# CH32V205RCT-R0.net
KiCad netlist of a schematic drawn in Altium Designer
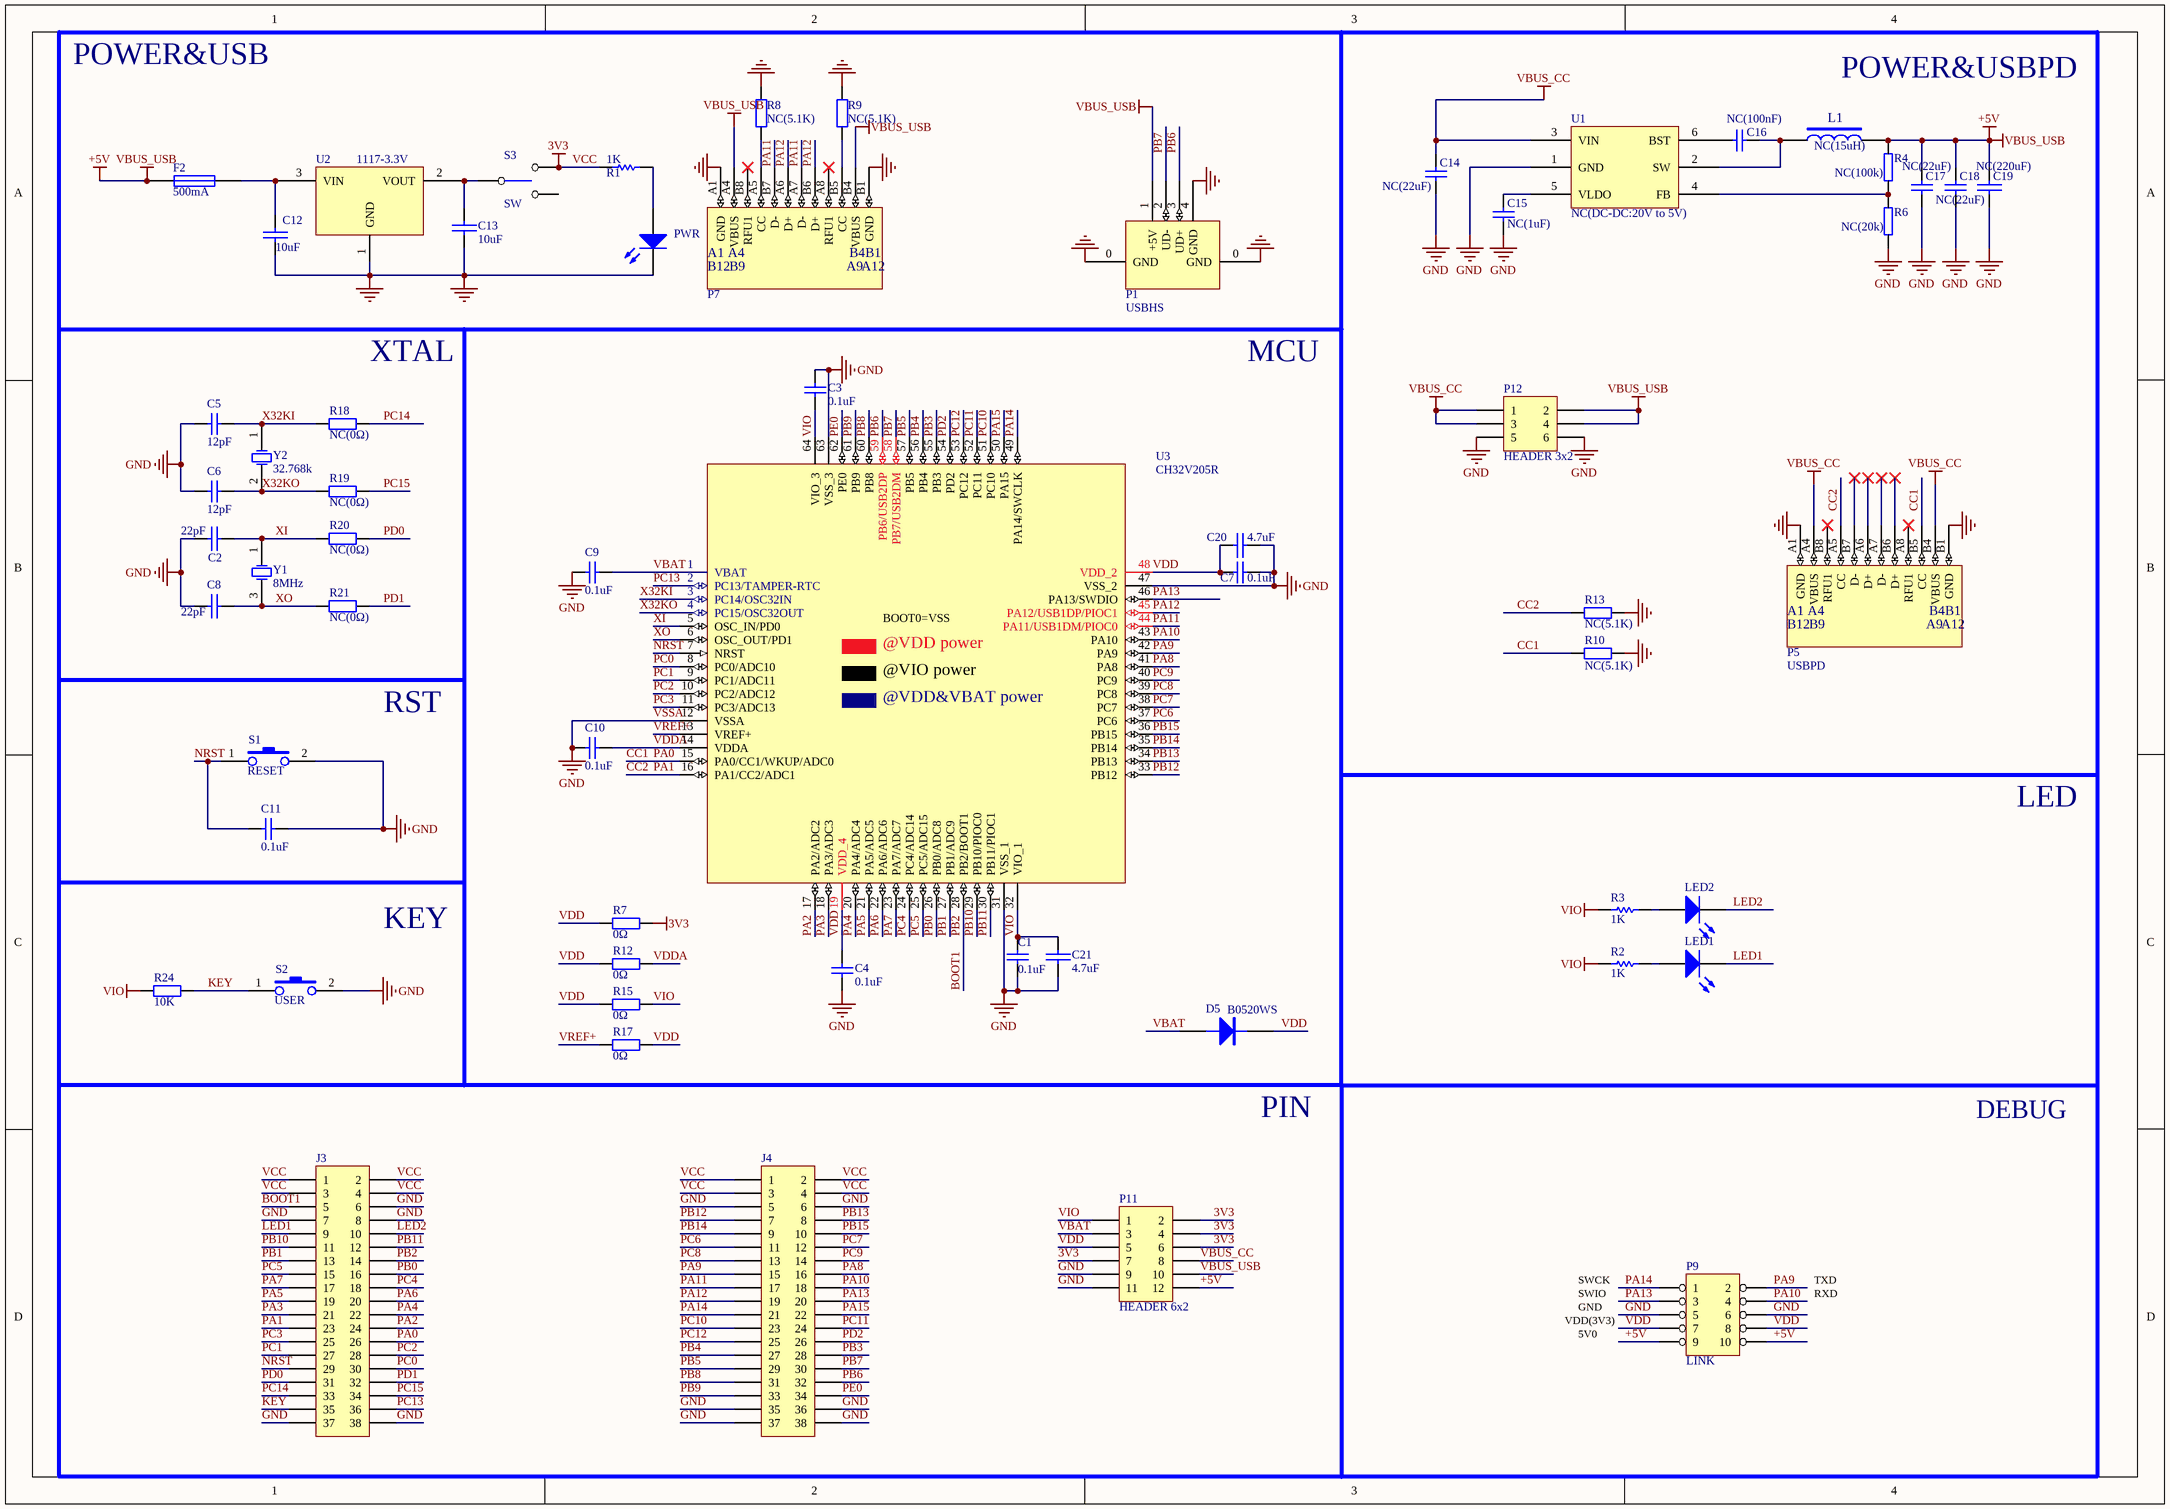
[diagram p0: CH32V205RCT-R0.SchDoc]

(export (version "E")
  (design (tool "Eeschema 10.0.6"))
  (components
    (comp (ref "C1")
      (value "0.1uF")
      (footprint "0402_C")
      (description "Capacitor")
      (libsource (lib "Miscellaneous Devices") (part "Cap"))
    )
    (comp (ref "C2")
      (value "22pF")
      (footprint "0402_C")
      (description "Capacitor")
      (libsource (lib "*") (part "CAP"))
    )
    (comp (ref "C3")
      (value "0.1uF")
      (footprint "0402_C")
      (description "Capacitor")
      (libsource (lib "Miscellaneous Devices") (part "Cap"))
    )
    (comp (ref "C4")
      (value "0.1uF")
      (footprint "0402_C")
      (description "Capacitor")
      (libsource (lib "Miscellaneous Devices") (part "Cap"))
    )
    (comp (ref "C5")
      (value "12pF")
      (footprint "0402_C")
      (description "Capacitor")
      (libsource (lib "Miscellaneous Devices") (part "Cap"))
    )
    (comp (ref "C6")
      (value "12pF")
      (footprint "0402_C")
      (description "Capacitor")
      (libsource (lib "Miscellaneous Devices") (part "Cap"))
    )
    (comp (ref "C7")
      (value "0.1uF")
      (footprint "0402_C")
      (description "Capacitor")
      (libsource (lib "Miscellaneous Devices") (part "Cap"))
    )
    (comp (ref "C8")
      (value "22pF")
      (footprint "0402_C")
      (description "Capacitor")
      (libsource (lib "*") (part "CAP"))
    )
    (comp (ref "C9")
      (value "0.1uF")
      (footprint "0402_C")
      (description "Capacitor")
      (libsource (lib "Miscellaneous Devices") (part "Cap"))
    )
    (comp (ref "C10")
      (value "0.1uF")
      (footprint "0402_C")
      (description "Capacitor")
      (libsource (lib "Miscellaneous Devices") (part "Cap"))
    )
    (comp (ref "C11")
      (value "0.1uF")
      (footprint "0402_C")
      (description "Capacitor")
      (libsource (lib "Miscellaneous Devices") (part "Cap"))
    )
    (comp (ref "C12")
      (value "10uF")
      (footprint "0805_C")
      (description "Capacitor")
      (libsource (lib "*") (part "CAP"))
    )
    (comp (ref "C13")
      (value "10uF")
      (footprint "0805_C")
      (description "Capacitor")
      (libsource (lib "*") (part "CAP"))
    )
    (comp (ref "C14")
      (value "NC(22uF)")
      (footprint "0805_C")
      (description "贴片电容")
      (libsource (lib "Miscellaneous Devices LC") (part "0603 100nF (104) 10% 50V"))
    )
    (comp (ref "C15")
      (value "NC(1uF)")
      (footprint "0402_C")
      (description "贴片电容")
      (libsource (lib "Miscellaneous Devices LC") (part "0603 100nF (104) 10% 50V"))
    )
    (comp (ref "C16")
      (value "NC(100nF)")
      (footprint "0402_C")
      (description "贴片电容")
      (libsource (lib "Miscellaneous Devices LC") (part "0603 100nF (104) 10% 50V"))
    )
    (comp (ref "C17")
      (value "NC(22uF)")
      (footprint "0805_C")
      (description "贴片电容")
      (libsource (lib "Miscellaneous Devices LC") (part "0603 100nF (104) 10% 50V"))
    )
    (comp (ref "C18")
      (value "NC(22uF)")
      (footprint "0805_C")
      (description "贴片电容")
      (libsource (lib "Miscellaneous Devices LC") (part "0603 100nF (104) 10% 50V"))
    )
    (comp (ref "C19")
      (value "NC(220uF)")
      (footprint "CD0.1")
      (description "Capacitor")
      (libsource (lib "") (part "CAP_1"))
    )
    (comp (ref "C20")
      (value "4.7uF")
      (footprint "0402_C")
      (description "Capacitor")
      (libsource (lib "*") (part "CAP"))
    )
    (comp (ref "C21")
      (value "4.7uF")
      (footprint "0402_C")
      (description "Capacitor")
      (libsource (lib "*") (part "CAP"))
    )
    (comp (ref "D5")
      (value "B0520WS")
      (footprint "SOD-323")
      (description "Diode")
      (libsource (lib "*") (part "DIODE"))
    )
    (comp (ref "F2")
      (value "500mA")
      (footprint "0805")
      (description "Fuse")
      (libsource (lib "*") (part "FUSE1"))
    )
    (comp (ref "J3")
      (value "Header 19X2")
      (footprint "IDC38-2.54mm")
      (description "Header, 19-Pin, Dual row")
      (fields (field (name "PUBLISHER") "Altium Limited"))
      (libsource (lib "Miscellaneous Connectors") (part "Header 19X2"))
    )
    (comp (ref "J4")
      (value "Header 19X2")
      (footprint "IDC38-2.54mm")
      (description "Header, 19-Pin, Dual row")
      (fields (field (name "PUBLISHER") "Altium Limited"))
      (libsource (lib "Miscellaneous Connectors") (part "Header 19X2"))
    )
    (comp (ref "L1")
      (value "NC(15uH)")
      (footprint "SMD_6x6mm")
      (libsource (lib "wch_sch_others") (part "INDUCTOR"))
    )
    (comp (ref "LED1")
      (value "LED1   blue")
      (footprint "0603+")
      (description "Typical INFRARED GaAs LED")
      (fields (field (name "PUBLISHER") "Altium Limited"))
      (libsource (lib "Miscellaneous Devices") (part "LED0"))
    )
    (comp (ref "LED2")
      (value "LED2  blue")
      (footprint "0603+")
      (description "Typical INFRARED GaAs LED")
      (fields (field (name "PUBLISHER") "Altium Limited"))
      (libsource (lib "Miscellaneous Devices") (part "LED0"))
    )
    (comp (ref "P1")
      (value "USBHS")
      (footprint "USBAF")
      (description "USB Port")
      (libsource (lib "*") (part "USB"))
    )
    (comp (ref "P5")
      (value "USBPD")
      (footprint "TYPE-C-Receptacle-2.0")
      (libsource (lib "*") (part "TYPE-C1"))
    )
    (comp (ref "P7")
      (value "TYPE-C")
      (footprint "TYPE-C-Receptacle-2.0")
      (libsource (lib "*") (part "TYPE-C1"))
    )
    (comp (ref "P9")
      (value "LINK")
      (footprint "MYPCB:IDC10-2.54mm")
      (description "Header, 5-Pin, Dual row")
      (libsource (lib "wch_sch_others") (part "HEADER 5x2"))
    )
    (comp (ref "P11")
      (value "HEADER 6x2")
      (footprint "MYPCB:IDC12-2.54mm")
      (description "Header, 6-Pin, Dual row")
      (libsource (lib "wch_sch_others") (part "HEADER 6x2"))
    )
    (comp (ref "P12")
      (value "HEADER 3x2")
      (footprint "MYPCB:IDC6-2.54mm")
      (description "Header, 3-Pin, Dual row")
      (libsource (lib "wch_sch_others") (part "HEADER 3x2"))
    )
    (comp (ref "PWR")
      (value "POWER  red")
      (footprint "0603+")
      (description "Typical INFRARED GaAs LED")
      (fields (field (name "PUBLISHER") "Altium Limited"))
      (libsource (lib "Miscellaneous Devices") (part "LED0"))
    )
    (comp (ref "R1")
      (value "1K")
      (footprint "0402")
      (description "Semiconductor Resistor")
      (libsource (lib "Miscellaneous Devices") (part "Res Semi"))
    )
    (comp (ref "R2")
      (value "1K")
      (footprint "0402")
      (description "Semiconductor Resistor")
      (libsource (lib "Miscellaneous Devices") (part "Res Semi"))
    )
    (comp (ref "R3")
      (value "1K")
      (footprint "0402")
      (description "Semiconductor Resistor")
      (libsource (lib "Miscellaneous Devices") (part "Res Semi"))
    )
    (comp (ref "R4") (value "NC(100k)") (footprint "0402") (libsource (lib "wch_sch_others") (part "RES")))
    (comp (ref "R6") (value "NC(20k)") (footprint "0402") (libsource (lib "wch_sch_others") (part "RES")))
    (comp (ref "R7")
      (value "0Ω")
      (footprint "0402")
      (description "Resistor")
      (libsource (lib "Miscellaneous Devices") (part "Res2"))
    )
    (comp (ref "R8")
      (value "NC(5.1K)")
      (footprint "0402")
      (description "Resistor")
      (libsource (lib "") (part "Res2_1"))
    )
    (comp (ref "R9")
      (value "NC(5.1K)")
      (footprint "0402")
      (description "Resistor")
      (libsource (lib "") (part "Res2_1"))
    )
    (comp (ref "R10")
      (value "NC(5.1K)")
      (footprint "0402")
      (description "Resistor")
      (libsource (lib "") (part "Res2_2"))
    )
    (comp (ref "R12")
      (value "0Ω")
      (footprint "0402")
      (description "Resistor")
      (libsource (lib "Miscellaneous Devices") (part "Res2"))
    )
    (comp (ref "R13")
      (value "NC(5.1K)")
      (footprint "0402")
      (description "Resistor")
      (libsource (lib "") (part "Res2_2"))
    )
    (comp (ref "R15")
      (value "0Ω")
      (footprint "0402")
      (description "Resistor")
      (libsource (lib "Miscellaneous Devices") (part "Res2"))
    )
    (comp (ref "R17")
      (value "0Ω")
      (footprint "0402")
      (description "Resistor")
      (libsource (lib "Miscellaneous Devices") (part "Res2"))
    )
    (comp (ref "R18")
      (value "NC(0Ω)")
      (footprint "0402")
      (description "Resistor")
      (libsource (lib "") (part "Res2_2"))
    )
    (comp (ref "R19")
      (value "NC(0Ω)")
      (footprint "0402")
      (description "Resistor")
      (libsource (lib "Miscellaneous Devices") (part "Res2"))
    )
    (comp (ref "R20")
      (value "NC(0Ω)")
      (footprint "0402")
      (description "Resistor")
      (libsource (lib "Miscellaneous Devices") (part "Res2"))
    )
    (comp (ref "R21")
      (value "NC(0Ω)")
      (footprint "0402")
      (description "Resistor")
      (libsource (lib "Miscellaneous Devices") (part "Res2"))
    )
    (comp (ref "R24")
      (value "10K")
      (footprint "0402")
      (description "Resistor")
      (libsource (lib "Miscellaneous Devices") (part "Res2"))
    )
    (comp (ref "S1")
      (value "RESET")
      (footprint "SMD_6.1x3.65x2.5mm-KEY")
      (libsource (lib "wch_sch_others") (part "KEY1"))
    )
    (comp (ref "S2")
      (value "USER")
      (footprint "SMD_6.1x3.65x2.5mm-KEY")
      (libsource (lib "wch_sch_others") (part "KEY1"))
    )
    (comp (ref "S3") (value "SW") (footprint "SW1") (libsource (lib "MYSCH") (part "SW")))
    (comp (ref "U1")
      (value "NC(DC-DC:20V to 5V)")
      (footprint "SOT-23-6")
      (description "DCDC")
      (libsource (lib "wch_sch_others") (part "TPS54202"))
    )
    (comp (ref "U2")
      (value "1117-3.3V")
      (footprint "SOT-223")
      (libsource (lib "wch_sch_others") (part "1117-3.3V"))
    )
    (comp (ref "U3")
      (value "CH32V205R")
      (footprint "LQFP64")
      (description "RISC-V MCU, 192MHz, USB_480M, USB FS, PD, PIOC, ADC, TKEY, 2*OPA, 2*CMP")
      (libsource (lib "CHXXX") (part "CH32V205R"))
    )
    (comp (ref "Y1")
      (value "8MHz")
      (footprint "XT3225")
      (description "Crystal Oscillator")
      (fields (field (name "PUBLISHER") "Altium Limited"))
      (libsource (lib "*") (part "XTAL"))
    )
    (comp (ref "Y2")
      (value "32.768k")
      (footprint "FC-135")
      (description "Crystal Oscillator")
      (fields (field (name "PUBLISHER") "Altium Limited"))
      (libsource (lib "Miscellaneous Devices") (part "XTAL"))
    )
  )
  (nets
    (net (code "1") (name "+5V") (class "Default")
      (node (ref "C17") (pin "2") (pinfunction "2_2") (pintype "passive"))
      (node (ref "C18") (pin "2") (pinfunction "2_2") (pintype "passive"))
      (node (ref "C19") (pin "1") (pinfunction "1_1") (pintype "passive"))
      (node (ref "F2") (pin "1") (pinfunction "1_1") (pintype "passive"))
      (node (ref "L1") (pin "2") (pinfunction "2_2") (pintype "passive"))
      (node (ref "P1") (pin "1") (pinfunction "+5V_1") (pintype "power_in"))
      (node (ref "P11") (pin "10") (pinfunction "10_10") (pintype "passive"))
      (node (ref "P11") (pin "12") (pinfunction "12_12") (pintype "passive"))
      (node (ref "P12") (pin "2") (pinfunction "2_2") (pintype "passive"))
      (node (ref "P12") (pin "4") (pinfunction "4_4") (pintype "passive"))
      (node (ref "P7") (pin "A4") (pinfunction "VBUS_A4") (pintype "bidirectional"))
      (node (ref "P7") (pin "B4") (pinfunction "VBUS_B4") (pintype "bidirectional"))
      (node (ref "P9") (pin "10") (pinfunction "10_10") (pintype "passive"))
      (node (ref "P9") (pin "9") (pinfunction "9_9") (pintype "passive"))
      (node (ref "R4") (pin "2") (pintype "passive"))
    )
    (net (code "3") (name "/BOOT1") (class "Default")
      (node (ref "J3") (pin "14") (pinfunction "14_14") (pintype "passive"))
      (node (ref "J3") (pin "5") (pinfunction "5_5") (pintype "passive"))
      (node (ref "U3") (pin "28") (pinfunction "PB2/BOOT1_28") (pintype "bidirectional"))
    )
    (net (code "4") (name "/CC1") (class "Default")
      (node (ref "J3") (pin "26") (pinfunction "26_26") (pintype "passive"))
      (node (ref "P5") (pin "B5") (pinfunction "CC_B5") (pintype "bidirectional"))
      (node (ref "R10") (pin "1") (pinfunction "1_1") (pintype "passive"))
      (node (ref "U3") (pin "15") (pinfunction "PA0/CC1/WKUP/ADC0_15") (pintype "bidirectional"))
    )
    (net (code "5") (name "/CC2") (class "Default")
      (node (ref "J3") (pin "23") (pinfunction "23_23") (pintype "passive"))
      (node (ref "P5") (pin "A5") (pinfunction "CC_A5") (pintype "bidirectional"))
      (node (ref "R13") (pin "1") (pinfunction "1_1") (pintype "passive"))
      (node (ref "U3") (pin "16") (pinfunction "PA1/CC2/ADC1_16") (pintype "bidirectional"))
    )
    (net (code "6") (name "/KEY") (class "Default")
      (node (ref "J3") (pin "35") (pinfunction "35_35") (pintype "passive"))
      (node (ref "R24") (pin "1") (pinfunction "1_1") (pintype "passive"))
      (node (ref "S2") (pin "1") (pinfunction "1_1") (pintype "passive"))
    )
    (net (code "7") (name "/LED1") (class "Default")
      (node (ref "J3") (pin "9") (pinfunction "9_9") (pintype "passive"))
      (node (ref "LED1") (pin "2") (pinfunction "K_2") (pintype "passive"))
    )
    (net (code "8") (name "/LED2") (class "Default")
      (node (ref "J3") (pin "10") (pinfunction "10_10") (pintype "passive"))
      (node (ref "LED2") (pin "2") (pinfunction "K_2") (pintype "passive"))
    )
    (net (code "9") (name "/NRST") (class "Default")
      (node (ref "C11") (pin "2") (pinfunction "2_2") (pintype "passive"))
      (node (ref "J3") (pin "29") (pinfunction "29_29") (pintype "passive"))
      (node (ref "S1") (pin "1") (pinfunction "1_1") (pintype "passive"))
      (node (ref "U3") (pin "7") (pinfunction "NRST_7") (pintype "input"))
    )
    (net (code "10") (name "/PA2") (class "Default")
      (node (ref "J3") (pin "24") (pinfunction "24_24") (pintype "passive"))
      (node (ref "U3") (pin "17") (pinfunction "PA2/ADC2_17") (pintype "bidirectional"))
    )
    (net (code "11") (name "/PA3") (class "Default")
      (node (ref "J3") (pin "21") (pinfunction "21_21") (pintype "passive"))
      (node (ref "U3") (pin "18") (pinfunction "PA3/ADC3_18") (pintype "bidirectional"))
    )
    (net (code "12") (name "/PA4") (class "Default")
      (node (ref "J3") (pin "22") (pinfunction "22_22") (pintype "passive"))
      (node (ref "U3") (pin "20") (pinfunction "PA4/ADC4_20") (pintype "bidirectional"))
    )
    (net (code "13") (name "/PA5") (class "Default")
      (node (ref "J3") (pin "19") (pinfunction "19_19") (pintype "passive"))
      (node (ref "U3") (pin "21") (pinfunction "PA5/ADC5_21") (pintype "bidirectional"))
    )
    (net (code "14") (name "/PA6") (class "Default")
      (node (ref "J3") (pin "20") (pinfunction "20_20") (pintype "passive"))
      (node (ref "U3") (pin "22") (pinfunction "PA6/ADC6_22") (pintype "bidirectional"))
    )
    (net (code "15") (name "/PA7") (class "Default")
      (node (ref "J3") (pin "17") (pinfunction "17_17") (pintype "passive"))
      (node (ref "U3") (pin "23") (pinfunction "PA7/ADC7_23") (pintype "bidirectional"))
    )
    (net (code "16") (name "/PA8") (class "Default")
      (node (ref "J4") (pin "16") (pinfunction "16_16") (pintype "passive"))
      (node (ref "U3") (pin "41") (pinfunction "PA8_41") (pintype "bidirectional"))
    )
    (net (code "17") (name "/PA9") (class "Default")
      (node (ref "J4") (pin "15") (pinfunction "15_15") (pintype "passive"))
      (node (ref "P9") (pin "2") (pinfunction "2_2") (pintype "passive"))
      (node (ref "U3") (pin "42") (pinfunction "PA9_42") (pintype "bidirectional"))
    )
    (net (code "18") (name "/PA10") (class "Default")
      (node (ref "J4") (pin "18") (pinfunction "18_18") (pintype "passive"))
      (node (ref "P9") (pin "4") (pinfunction "4_4") (pintype "passive"))
      (node (ref "U3") (pin "43") (pinfunction "PA10_43") (pintype "bidirectional"))
    )
    (net (code "19") (name "/PA11") (class "Default")
      (node (ref "J4") (pin "17") (pinfunction "17_17") (pintype "passive"))
      (node (ref "P7") (pin "A7") (pinfunction "D-_A7") (pintype "bidirectional"))
      (node (ref "P7") (pin "B7") (pinfunction "D-_B7") (pintype "bidirectional"))
      (node (ref "U3") (pin "44") (pinfunction "PA11/USB1DM/PIOC0_44") (pintype "bidirectional"))
    )
    (net (code "20") (name "/PA12") (class "Default")
      (node (ref "J4") (pin "19") (pinfunction "19_19") (pintype "passive"))
      (node (ref "P7") (pin "A6") (pinfunction "D+_A6") (pintype "bidirectional"))
      (node (ref "P7") (pin "B6") (pinfunction "D+_B6") (pintype "bidirectional"))
      (node (ref "U3") (pin "45") (pinfunction "PA12/USB1DP/PIOC1_45") (pintype "bidirectional"))
    )
    (net (code "21") (name "/PA13") (class "Default")
      (node (ref "J4") (pin "20") (pinfunction "20_20") (pintype "passive"))
      (node (ref "P9") (pin "3") (pinfunction "3_3") (pintype "passive"))
      (node (ref "U3") (pin "46") (pinfunction "PA13/SWDIO_46") (pintype "bidirectional"))
    )
    (net (code "22") (name "/PA14") (class "Default")
      (node (ref "J4") (pin "21") (pinfunction "21_21") (pintype "passive"))
      (node (ref "P9") (pin "1") (pinfunction "1_1") (pintype "passive"))
      (node (ref "U3") (pin "49") (pinfunction "PA14/SWCLK_49") (pintype "bidirectional"))
    )
    (net (code "23") (name "/PA15") (class "Default")
      (node (ref "J4") (pin "22") (pinfunction "22_22") (pintype "passive"))
      (node (ref "U3") (pin "50") (pinfunction "PA15_50") (pintype "bidirectional"))
    )
    (net (code "24") (name "/PB0") (class "Default")
      (node (ref "J3") (pin "16") (pinfunction "16_16") (pintype "passive"))
      (node (ref "U3") (pin "26") (pinfunction "PB0/ADC8_26") (pintype "bidirectional"))
    )
    (net (code "25") (name "/PB1") (class "Default")
      (node (ref "J3") (pin "13") (pinfunction "13_13") (pintype "passive"))
      (node (ref "U3") (pin "27") (pinfunction "PB1/ADC9_27") (pintype "bidirectional"))
    )
    (net (code "26") (name "/PB3") (class "Default")
      (node (ref "J4") (pin "28") (pinfunction "28_28") (pintype "passive"))
      (node (ref "U3") (pin "55") (pinfunction "PB3_55") (pintype "bidirectional"))
    )
    (net (code "27") (name "/PB4") (class "Default")
      (node (ref "J4") (pin "27") (pinfunction "27_27") (pintype "passive"))
      (node (ref "U3") (pin "56") (pinfunction "PB4_56") (pintype "bidirectional"))
    )
    (net (code "28") (name "/PB5") (class "Default")
      (node (ref "J4") (pin "29") (pinfunction "29_29") (pintype "passive"))
      (node (ref "U3") (pin "57") (pinfunction "PB5_57") (pintype "bidirectional"))
    )
    (net (code "29") (name "/PB6") (class "Default")
      (node (ref "J4") (pin "32") (pinfunction "32_32") (pintype "passive"))
      (node (ref "P1") (pin "3") (pinfunction "UD+_3") (pintype "bidirectional"))
      (node (ref "U3") (pin "59") (pinfunction "PB6/USB2DP_59") (pintype "bidirectional"))
    )
    (net (code "30") (name "/PB7") (class "Default")
      (node (ref "J4") (pin "30") (pinfunction "30_30") (pintype "passive"))
      (node (ref "P1") (pin "2") (pinfunction "UD-_2") (pintype "bidirectional"))
      (node (ref "U3") (pin "58") (pinfunction "PB7/USB2DM_58") (pintype "bidirectional"))
    )
    (net (code "31") (name "/PB8") (class "Default")
      (node (ref "J4") (pin "31") (pinfunction "31_31") (pintype "passive"))
      (node (ref "U3") (pin "60") (pinfunction "PB8_60") (pintype "bidirectional"))
    )
    (net (code "32") (name "/PB9") (class "Default")
      (node (ref "J4") (pin "33") (pinfunction "33_33") (pintype "passive"))
      (node (ref "U3") (pin "61") (pinfunction "PB9_61") (pintype "bidirectional"))
    )
    (net (code "33") (name "/PB10") (class "Default")
      (node (ref "J3") (pin "11") (pinfunction "11_11") (pintype "passive"))
      (node (ref "U3") (pin "29") (pinfunction "PB10/PIOC0_29") (pintype "bidirectional"))
    )
    (net (code "34") (name "/PB11") (class "Default")
      (node (ref "J3") (pin "12") (pinfunction "12_12") (pintype "passive"))
      (node (ref "U3") (pin "30") (pinfunction "PB11/PIOC1_30") (pintype "bidirectional"))
    )
    (net (code "35") (name "/PB12") (class "Default")
      (node (ref "J4") (pin "7") (pinfunction "7_7") (pintype "passive"))
      (node (ref "U3") (pin "33") (pinfunction "PB12_33") (pintype "bidirectional"))
    )
    (net (code "36") (name "/PB13") (class "Default")
      (node (ref "J4") (pin "8") (pinfunction "8_8") (pintype "passive"))
      (node (ref "U3") (pin "34") (pinfunction "PB13_34") (pintype "bidirectional"))
    )
    (net (code "37") (name "/PB14") (class "Default")
      (node (ref "J4") (pin "9") (pinfunction "9_9") (pintype "passive"))
      (node (ref "U3") (pin "35") (pinfunction "PB14_35") (pintype "bidirectional"))
    )
    (net (code "38") (name "/PB15") (class "Default")
      (node (ref "J4") (pin "10") (pinfunction "10_10") (pintype "passive"))
      (node (ref "U3") (pin "36") (pinfunction "PB15_36") (pintype "bidirectional"))
    )
    (net (code "39") (name "/PC0") (class "Default")
      (node (ref "J3") (pin "30") (pinfunction "30_30") (pintype "passive"))
      (node (ref "U3") (pin "8") (pinfunction "PC0/ADC10_8") (pintype "bidirectional"))
    )
    (net (code "40") (name "/PC1") (class "Default")
      (node (ref "J3") (pin "27") (pinfunction "27_27") (pintype "passive"))
      (node (ref "U3") (pin "9") (pinfunction "PC1/ADC11_9") (pintype "bidirectional"))
    )
    (net (code "41") (name "/PC2") (class "Default")
      (node (ref "J3") (pin "28") (pinfunction "28_28") (pintype "passive"))
      (node (ref "U3") (pin "10") (pinfunction "PC2/ADC12_10") (pintype "bidirectional"))
    )
    (net (code "42") (name "/PC3") (class "Default")
      (node (ref "J3") (pin "25") (pinfunction "25_25") (pintype "passive"))
      (node (ref "U3") (pin "11") (pinfunction "PC3/ADC13_11") (pintype "bidirectional"))
    )
    (net (code "43") (name "/PC4") (class "Default")
      (node (ref "J3") (pin "18") (pinfunction "18_18") (pintype "passive"))
      (node (ref "U3") (pin "24") (pinfunction "PC4/ADC14_24") (pintype "bidirectional"))
    )
    (net (code "44") (name "/PC5") (class "Default")
      (node (ref "J3") (pin "15") (pinfunction "15_15") (pintype "passive"))
      (node (ref "U3") (pin "25") (pinfunction "PC5/ADC15_25") (pintype "bidirectional"))
    )
    (net (code "45") (name "/PC6") (class "Default")
      (node (ref "J4") (pin "11") (pinfunction "11_11") (pintype "passive"))
      (node (ref "U3") (pin "37") (pinfunction "PC6_37") (pintype "bidirectional"))
    )
    (net (code "46") (name "/PC7") (class "Default")
      (node (ref "J4") (pin "12") (pinfunction "12_12") (pintype "passive"))
      (node (ref "U3") (pin "38") (pinfunction "PC7_38") (pintype "bidirectional"))
    )
    (net (code "47") (name "/PC8") (class "Default")
      (node (ref "J4") (pin "13") (pinfunction "13_13") (pintype "passive"))
      (node (ref "U3") (pin "39") (pinfunction "PC8_39") (pintype "bidirectional"))
    )
    (net (code "48") (name "/PC9") (class "Default")
      (node (ref "J4") (pin "14") (pinfunction "14_14") (pintype "passive"))
      (node (ref "U3") (pin "40") (pinfunction "PC9_40") (pintype "bidirectional"))
    )
    (net (code "49") (name "/PC10") (class "Default")
      (node (ref "J4") (pin "23") (pinfunction "23_23") (pintype "passive"))
      (node (ref "U3") (pin "51") (pinfunction "PC10_51") (pintype "bidirectional"))
    )
    (net (code "50") (name "/PC11") (class "Default")
      (node (ref "J4") (pin "24") (pinfunction "24_24") (pintype "passive"))
      (node (ref "U3") (pin "52") (pinfunction "PC11_52") (pintype "bidirectional"))
    )
    (net (code "51") (name "/PC12") (class "Default")
      (node (ref "J4") (pin "25") (pinfunction "25_25") (pintype "passive"))
      (node (ref "U3") (pin "53") (pinfunction "PC12_53") (pintype "bidirectional"))
    )
    (net (code "52") (name "/PC13") (class "Default")
      (node (ref "J3") (pin "36") (pinfunction "36_36") (pintype "passive"))
      (node (ref "U3") (pin "2") (pinfunction "PC13/TAMPER-RTC_2") (pintype "bidirectional"))
    )
    (net (code "53") (name "/PC14") (class "Default")
      (node (ref "J3") (pin "33") (pinfunction "33_33") (pintype "passive"))
      (node (ref "R18") (pin "2") (pinfunction "2_2") (pintype "passive"))
    )
    (net (code "54") (name "/PC15") (class "Default")
      (node (ref "J3") (pin "34") (pinfunction "34_34") (pintype "passive"))
      (node (ref "R19") (pin "1") (pinfunction "1_1") (pintype "passive"))
    )
    (net (code "55") (name "/PD0") (class "Default")
      (node (ref "J3") (pin "31") (pinfunction "31_31") (pintype "passive"))
      (node (ref "R20") (pin "1") (pinfunction "1_1") (pintype "passive"))
    )
    (net (code "56") (name "/PD1") (class "Default")
      (node (ref "J3") (pin "32") (pinfunction "32_32") (pintype "passive"))
      (node (ref "R21") (pin "1") (pinfunction "1_1") (pintype "passive"))
    )
    (net (code "57") (name "/PD2") (class "Default")
      (node (ref "J4") (pin "26") (pinfunction "26_26") (pintype "passive"))
      (node (ref "U3") (pin "54") (pinfunction "PD2_54") (pintype "bidirectional"))
    )
    (net (code "58") (name "/PE0") (class "Default")
      (node (ref "J4") (pin "34") (pinfunction "34_34") (pintype "passive"))
      (node (ref "U3") (pin "62") (pinfunction "PE0_62") (pintype "bidirectional"))
    )
    (net (code "59") (name "/VBAT") (class "Default")
      (node (ref "C9") (pin "1") (pinfunction "1_1") (pintype "passive"))
      (node (ref "D5") (pin "1") (pinfunction "A_1") (pintype "passive"))
      (node (ref "P11") (pin "3") (pinfunction "3_3") (pintype "passive"))
      (node (ref "U3") (pin "1") (pinfunction "VBAT_1") (pintype "power_in"))
    )
    (net (code "60") (name "/VDD") (class "Default")
      (node (ref "C20") (pin "1") (pinfunction "1_1") (pintype "passive"))
      (node (ref "C4") (pin "2") (pinfunction "2_2") (pintype "passive"))
      (node (ref "C7") (pin "2") (pinfunction "2_2") (pintype "passive"))
      (node (ref "D5") (pin "2") (pinfunction "K_2") (pintype "passive"))
      (node (ref "P11") (pin "5") (pinfunction "5_5") (pintype "passive"))
      (node (ref "P9") (pin "7") (pinfunction "7_7") (pintype "passive"))
      (node (ref "P9") (pin "8") (pinfunction "8_8") (pintype "passive"))
      (node (ref "R12") (pin "2") (pinfunction "2_2") (pintype "passive"))
      (node (ref "R15") (pin "2") (pinfunction "2_2") (pintype "passive"))
      (node (ref "R17") (pin "1") (pinfunction "1_1") (pintype "passive"))
      (node (ref "R7") (pin "2") (pinfunction "2_2") (pintype "passive"))
      (node (ref "U3") (pin "19") (pinfunction "VDD_4_19") (pintype "power_in"))
      (node (ref "U3") (pin "48") (pinfunction "VDD_2_48") (pintype "power_in"))
    )
    (net (code "61") (name "/VDDA") (class "Default")
      (node (ref "C10") (pin "1") (pinfunction "1_1") (pintype "passive"))
      (node (ref "R12") (pin "1") (pinfunction "1_1") (pintype "passive"))
      (node (ref "U3") (pin "14") (pinfunction "VDDA_14") (pintype "power_in"))
    )
    (net (code "62") (name "/VREF+") (class "Default")
      (node (ref "R17") (pin "2") (pinfunction "2_2") (pintype "passive"))
      (node (ref "U3") (pin "13") (pinfunction "VREF+_13") (pintype "power_in"))
    )
    (net (code "63") (name "/X32KI") (class "Default")
      (node (ref "C5") (pin "1") (pinfunction "1_1") (pintype "passive"))
      (node (ref "R18") (pin "1") (pinfunction "1_1") (pintype "passive"))
      (node (ref "U3") (pin "3") (pinfunction "PC14/OSC32IN_3") (pintype "bidirectional"))
      (node (ref "Y2") (pin "1") (pinfunction "OSC1_1") (pintype "passive"))
    )
    (net (code "64") (name "/X32KO") (class "Default")
      (node (ref "C6") (pin "1") (pinfunction "1_1") (pintype "passive"))
      (node (ref "R19") (pin "2") (pinfunction "2_2") (pintype "passive"))
      (node (ref "U3") (pin "4") (pinfunction "PC15/OSC32OUT_4") (pintype "bidirectional"))
      (node (ref "Y2") (pin "2") (pinfunction "OSC2_2") (pintype "passive"))
    )
    (net (code "65") (name "/XI") (class "Default")
      (node (ref "C2") (pin "2") (pinfunction "2_2") (pintype "passive"))
      (node (ref "R20") (pin "2") (pinfunction "2_2") (pintype "passive"))
      (node (ref "U3") (pin "5") (pinfunction "OSC_IN/PD0_5") (pintype "bidirectional"))
      (node (ref "Y1") (pin "1") (pinfunction "OSC1_1") (pintype "passive"))
    )
    (net (code "66") (name "/XO") (class "Default")
      (node (ref "C8") (pin "2") (pinfunction "2_2") (pintype "passive"))
      (node (ref "R21") (pin "2") (pinfunction "2_2") (pintype "passive"))
      (node (ref "U3") (pin "6") (pinfunction "OSC_OUT/PD1_6") (pintype "bidirectional"))
      (node (ref "Y1") (pin "3") (pinfunction "OSC2_3") (pintype "passive"))
    )
    (net (code "67") (name "3V3") (class "Default")
      (node (ref "J3") (pin "1") (pinfunction "1_1") (pintype "passive"))
      (node (ref "J3") (pin "2") (pinfunction "2_2") (pintype "passive"))
      (node (ref "J3") (pin "3") (pinfunction "3_3") (pintype "passive"))
      (node (ref "J3") (pin "4") (pinfunction "4_4") (pintype "passive"))
      (node (ref "J4") (pin "1") (pinfunction "1_1") (pintype "passive"))
      (node (ref "J4") (pin "2") (pinfunction "2_2") (pintype "passive"))
      (node (ref "J4") (pin "3") (pinfunction "3_3") (pintype "passive"))
      (node (ref "J4") (pin "4") (pinfunction "4_4") (pintype "passive"))
      (node (ref "P11") (pin "2") (pinfunction "2_2") (pintype "passive"))
      (node (ref "P11") (pin "4") (pinfunction "4_4") (pintype "passive"))
      (node (ref "P11") (pin "6") (pinfunction "6_6") (pintype "passive"))
      (node (ref "P11") (pin "7") (pinfunction "7_7") (pintype "passive"))
      (node (ref "R1") (pin "2") (pinfunction "2_2") (pintype "passive"))
      (node (ref "R7") (pin "1") (pinfunction "1_1") (pintype "passive"))
      (node (ref "S3") (pin "3") (pinfunction "3_3") (pintype "passive"))
    )
    (net (code "68") (name "GND") (class "Default")
      (node (ref "C1") (pin "1") (pinfunction "1_1") (pintype "passive"))
      (node (ref "C10") (pin "2") (pinfunction "2_2") (pintype "passive"))
      (node (ref "C11") (pin "1") (pinfunction "1_1") (pintype "passive"))
      (node (ref "C12") (pin "2") (pinfunction "2_2") (pintype "passive"))
      (node (ref "C13") (pin "2") (pinfunction "2_2") (pintype "passive"))
      (node (ref "C14") (pin "1") (pinfunction "1_1") (pintype "passive"))
      (node (ref "C15") (pin "1") (pinfunction "1_1") (pintype "passive"))
      (node (ref "C17") (pin "1") (pinfunction "1_1") (pintype "passive"))
      (node (ref "C18") (pin "1") (pinfunction "1_1") (pintype "passive"))
      (node (ref "C19") (pin "2") (pinfunction "2_2") (pintype "passive"))
      (node (ref "C2") (pin "1") (pinfunction "1_1") (pintype "passive"))
      (node (ref "C20") (pin "2") (pinfunction "2_2") (pintype "passive"))
      (node (ref "C21") (pin "1") (pinfunction "1_1") (pintype "passive"))
      (node (ref "C3") (pin "1") (pinfunction "1_1") (pintype "passive"))
      (node (ref "C4") (pin "1") (pinfunction "1_1") (pintype "passive"))
      (node (ref "C5") (pin "2") (pinfunction "2_2") (pintype "passive"))
      (node (ref "C6") (pin "2") (pinfunction "2_2") (pintype "passive"))
      (node (ref "C7") (pin "1") (pinfunction "1_1") (pintype "passive"))
      (node (ref "C8") (pin "1") (pinfunction "1_1") (pintype "passive"))
      (node (ref "C9") (pin "2") (pinfunction "2_2") (pintype "passive"))
      (node (ref "J3") (pin "37") (pinfunction "37_37") (pintype "passive"))
      (node (ref "J3") (pin "38") (pinfunction "38_38") (pintype "passive"))
      (node (ref "J3") (pin "6") (pinfunction "6_6") (pintype "passive"))
      (node (ref "J3") (pin "7") (pinfunction "7_7") (pintype "passive"))
      (node (ref "J3") (pin "8") (pinfunction "8_8") (pintype "passive"))
      (node (ref "J4") (pin "35") (pinfunction "35_35") (pintype "passive"))
      (node (ref "J4") (pin "36") (pinfunction "36_36") (pintype "passive"))
      (node (ref "J4") (pin "37") (pinfunction "37_37") (pintype "passive"))
      (node (ref "J4") (pin "38") (pinfunction "38_38") (pintype "passive"))
      (node (ref "J4") (pin "5") (pinfunction "5_5") (pintype "passive"))
      (node (ref "J4") (pin "6") (pinfunction "6_6") (pintype "passive"))
      (node (ref "P1") (pin "0") (pinfunction "GND_0") (pintype "power_in"))
      (node (ref "P1") (pin "4") (pinfunction "GND_4") (pintype "power_in"))
      (node (ref "P11") (pin "11") (pinfunction "11_11") (pintype "passive"))
      (node (ref "P11") (pin "9") (pinfunction "9_9") (pintype "passive"))
      (node (ref "P12") (pin "5") (pinfunction "5_5") (pintype "passive"))
      (node (ref "P12") (pin "6") (pinfunction "6_6") (pintype "passive"))
      (node (ref "P5") (pin "A1") (pinfunction "GND_A1") (pintype "bidirectional"))
      (node (ref "P5") (pin "B1") (pinfunction "GND_B1") (pintype "bidirectional"))
      (node (ref "P7") (pin "A1") (pinfunction "GND_A1") (pintype "bidirectional"))
      (node (ref "P7") (pin "B1") (pinfunction "GND_B1") (pintype "bidirectional"))
      (node (ref "P9") (pin "5") (pinfunction "5_5") (pintype "passive"))
      (node (ref "P9") (pin "6") (pinfunction "6_6") (pintype "passive"))
      (node (ref "PWR") (pin "2") (pinfunction "K_2") (pintype "passive"))
      (node (ref "R10") (pin "2") (pinfunction "2_2") (pintype "passive"))
      (node (ref "R13") (pin "2") (pinfunction "2_2") (pintype "passive"))
      (node (ref "R6") (pin "1") (pintype "passive"))
      (node (ref "R8") (pin "1") (pinfunction "1_1") (pintype "passive"))
      (node (ref "R9") (pin "1") (pinfunction "1_1") (pintype "passive"))
      (node (ref "S1") (pin "2") (pinfunction "2_2") (pintype "passive"))
      (node (ref "S2") (pin "2") (pinfunction "2_2") (pintype "passive"))
      (node (ref "U1") (pin "1") (pinfunction "GND_1") (pintype "passive"))
      (node (ref "U2") (pin "1") (pinfunction "GND_1") (pintype "passive"))
      (node (ref "U3") (pin "12") (pinfunction "VSSA_12") (pintype "power_in"))
      (node (ref "U3") (pin "31") (pinfunction "VSS_1_31") (pintype "power_in"))
      (node (ref "U3") (pin "47") (pinfunction "VSS_2_47") (pintype "power_in"))
      (node (ref "U3") (pin "63") (pinfunction "VSS_3_63") (pintype "power_in"))
    )
    (net (code "69") (name "Net-(LED1-A)") (class "Default")
      (node (ref "LED1") (pin "1") (pinfunction "A_1") (pintype "passive"))
      (node (ref "R2") (pin "2") (pinfunction "2_2") (pintype "passive"))
    )
    (net (code "70") (name "Net-(LED2-A)") (class "Default")
      (node (ref "LED2") (pin "1") (pinfunction "A_1") (pintype "passive"))
      (node (ref "R3") (pin "2") (pinfunction "2_2") (pintype "passive"))
    )
    (net (code "71") (name "Net-(P7-CC-PadA5)") (class "Default")
      (node (ref "P7") (pin "A5") (pinfunction "CC_A5") (pintype "bidirectional"))
      (node (ref "R8") (pin "2") (pinfunction "2_2") (pintype "passive"))
    )
    (net (code "72") (name "Net-(P7-CC-PadB5)") (class "Default")
      (node (ref "P7") (pin "B5") (pinfunction "CC_B5") (pintype "bidirectional"))
      (node (ref "R9") (pin "2") (pinfunction "2_2") (pintype "passive"))
    )
    (net (code "73") (name "Net-(PWR-A)") (class "Default")
      (node (ref "PWR") (pin "1") (pinfunction "A_1") (pintype "passive"))
      (node (ref "R1") (pin "1") (pinfunction "1_1") (pintype "passive"))
    )
    (net (code "74") (name "Net-(U1-BST)") (class "Default")
      (node (ref "C16") (pin "2") (pinfunction "2_2") (pintype "passive"))
      (node (ref "U1") (pin "6") (pinfunction "BST_6") (pintype "passive"))
    )
    (net (code "75") (name "Net-(U1-FB)") (class "Default")
      (node (ref "R4") (pin "1") (pintype "passive"))
      (node (ref "R6") (pin "2") (pintype "passive"))
      (node (ref "U1") (pin "4") (pinfunction "FB_4") (pintype "passive"))
    )
    (net (code "76") (name "Net-(U1-SW)") (class "Default")
      (node (ref "C16") (pin "1") (pinfunction "1_1") (pintype "passive"))
      (node (ref "L1") (pin "1") (pinfunction "1_1") (pintype "passive"))
      (node (ref "U1") (pin "2") (pinfunction "SW_2") (pintype "passive"))
    )
    (net (code "77") (name "Net-(U1-VLDO)") (class "Default")
      (node (ref "C15") (pin "2") (pinfunction "2_2") (pintype "passive"))
      (node (ref "U1") (pin "5") (pinfunction "VLDO_5") (pintype "passive"))
    )
    (net (code "78") (name "Net-(U2-VIN)") (class "Default")
      (node (ref "C12") (pin "1") (pinfunction "1_1") (pintype "passive"))
      (node (ref "F2") (pin "2") (pinfunction "2_2") (pintype "passive"))
      (node (ref "U2") (pin "3") (pinfunction "VIN_3") (pintype "passive"))
    )
    (net (code "79") (name "Net-(U2-VOUT)") (class "Default")
      (node (ref "C13") (pin "1") (pinfunction "1_1") (pintype "passive"))
      (node (ref "S3") (pin "1") (pinfunction "1_1") (pintype "passive"))
      (node (ref "U2") (pin "2") (pinfunction "VOUT_2") (pintype "passive"))
    )
    (net (code "80") (name "VBUS_CC") (class "Default")
      (node (ref "C14") (pin "2") (pinfunction "2_2") (pintype "passive"))
      (node (ref "P11") (pin "8") (pinfunction "8_8") (pintype "passive"))
      (node (ref "P12") (pin "1") (pinfunction "1_1") (pintype "passive"))
      (node (ref "P12") (pin "3") (pinfunction "3_3") (pintype "passive"))
      (node (ref "P5") (pin "A4") (pinfunction "VBUS_A4") (pintype "bidirectional"))
      (node (ref "P5") (pin "B4") (pinfunction "VBUS_B4") (pintype "bidirectional"))
      (node (ref "U1") (pin "3") (pinfunction "VIN_3") (pintype "passive"))
    )
    (net (code "81") (name "VIO") (class "Default")
      (node (ref "C1") (pin "2") (pinfunction "2_2") (pintype "passive"))
      (node (ref "C21") (pin "2") (pinfunction "2_2") (pintype "passive"))
      (node (ref "C3") (pin "2") (pinfunction "2_2") (pintype "passive"))
      (node (ref "P11") (pin "1") (pinfunction "1_1") (pintype "passive"))
      (node (ref "R15") (pin "1") (pinfunction "1_1") (pintype "passive"))
      (node (ref "R2") (pin "1") (pinfunction "1_1") (pintype "passive"))
      (node (ref "R24") (pin "2") (pinfunction "2_2") (pintype "passive"))
      (node (ref "R3") (pin "1") (pinfunction "1_1") (pintype "passive"))
      (node (ref "U3") (pin "32") (pinfunction "VIO_1_32") (pintype "power_in"))
      (node (ref "U3") (pin "64") (pinfunction "VIO_3_64") (pintype "power_in"))
    )
    (net (code "82") (name "unconnected-(P5-D+-PadA6)") (class "Default")
      (node (ref "P5") (pin "A6") (pinfunction "D+_A6") (pintype "bidirectional+no_connect"))
    )
    (net (code "83") (name "unconnected-(P5-D+-PadB6)") (class "Default")
      (node (ref "P5") (pin "B6") (pinfunction "D+_B6") (pintype "bidirectional+no_connect"))
    )
    (net (code "84") (name "unconnected-(P5-D--PadA7)") (class "Default")
      (node (ref "P5") (pin "A7") (pinfunction "D-_A7") (pintype "bidirectional+no_connect"))
    )
    (net (code "85") (name "unconnected-(P5-D--PadB7)") (class "Default")
      (node (ref "P5") (pin "B7") (pinfunction "D-_B7") (pintype "bidirectional+no_connect"))
    )
    (net (code "86") (name "unconnected-(P5-RFU1-PadA8)") (class "Default")
      (node (ref "P5") (pin "A8") (pinfunction "RFU1_A8") (pintype "bidirectional+no_connect"))
    )
    (net (code "87") (name "unconnected-(P5-RFU1-PadB8)") (class "Default")
      (node (ref "P5") (pin "B8") (pinfunction "RFU1_B8") (pintype "bidirectional+no_connect"))
    )
    (net (code "88") (name "unconnected-(P7-RFU1-PadA8)") (class "Default")
      (node (ref "P7") (pin "A8") (pinfunction "RFU1_A8") (pintype "bidirectional+no_connect"))
    )
    (net (code "89") (name "unconnected-(P7-RFU1-PadB8)") (class "Default")
      (node (ref "P7") (pin "B8") (pinfunction "RFU1_B8") (pintype "bidirectional+no_connect"))
    )
    (net (code "90") (name "unconnected-(S3-Pad2)") (class "Default")
      (node (ref "S3") (pin "2") (pinfunction "2_2") (pintype "passive"))
    )
  )
)
